# P18_USB_3_0_DRD.net
KiCad netlist of a schematic drawn in Altium Designer
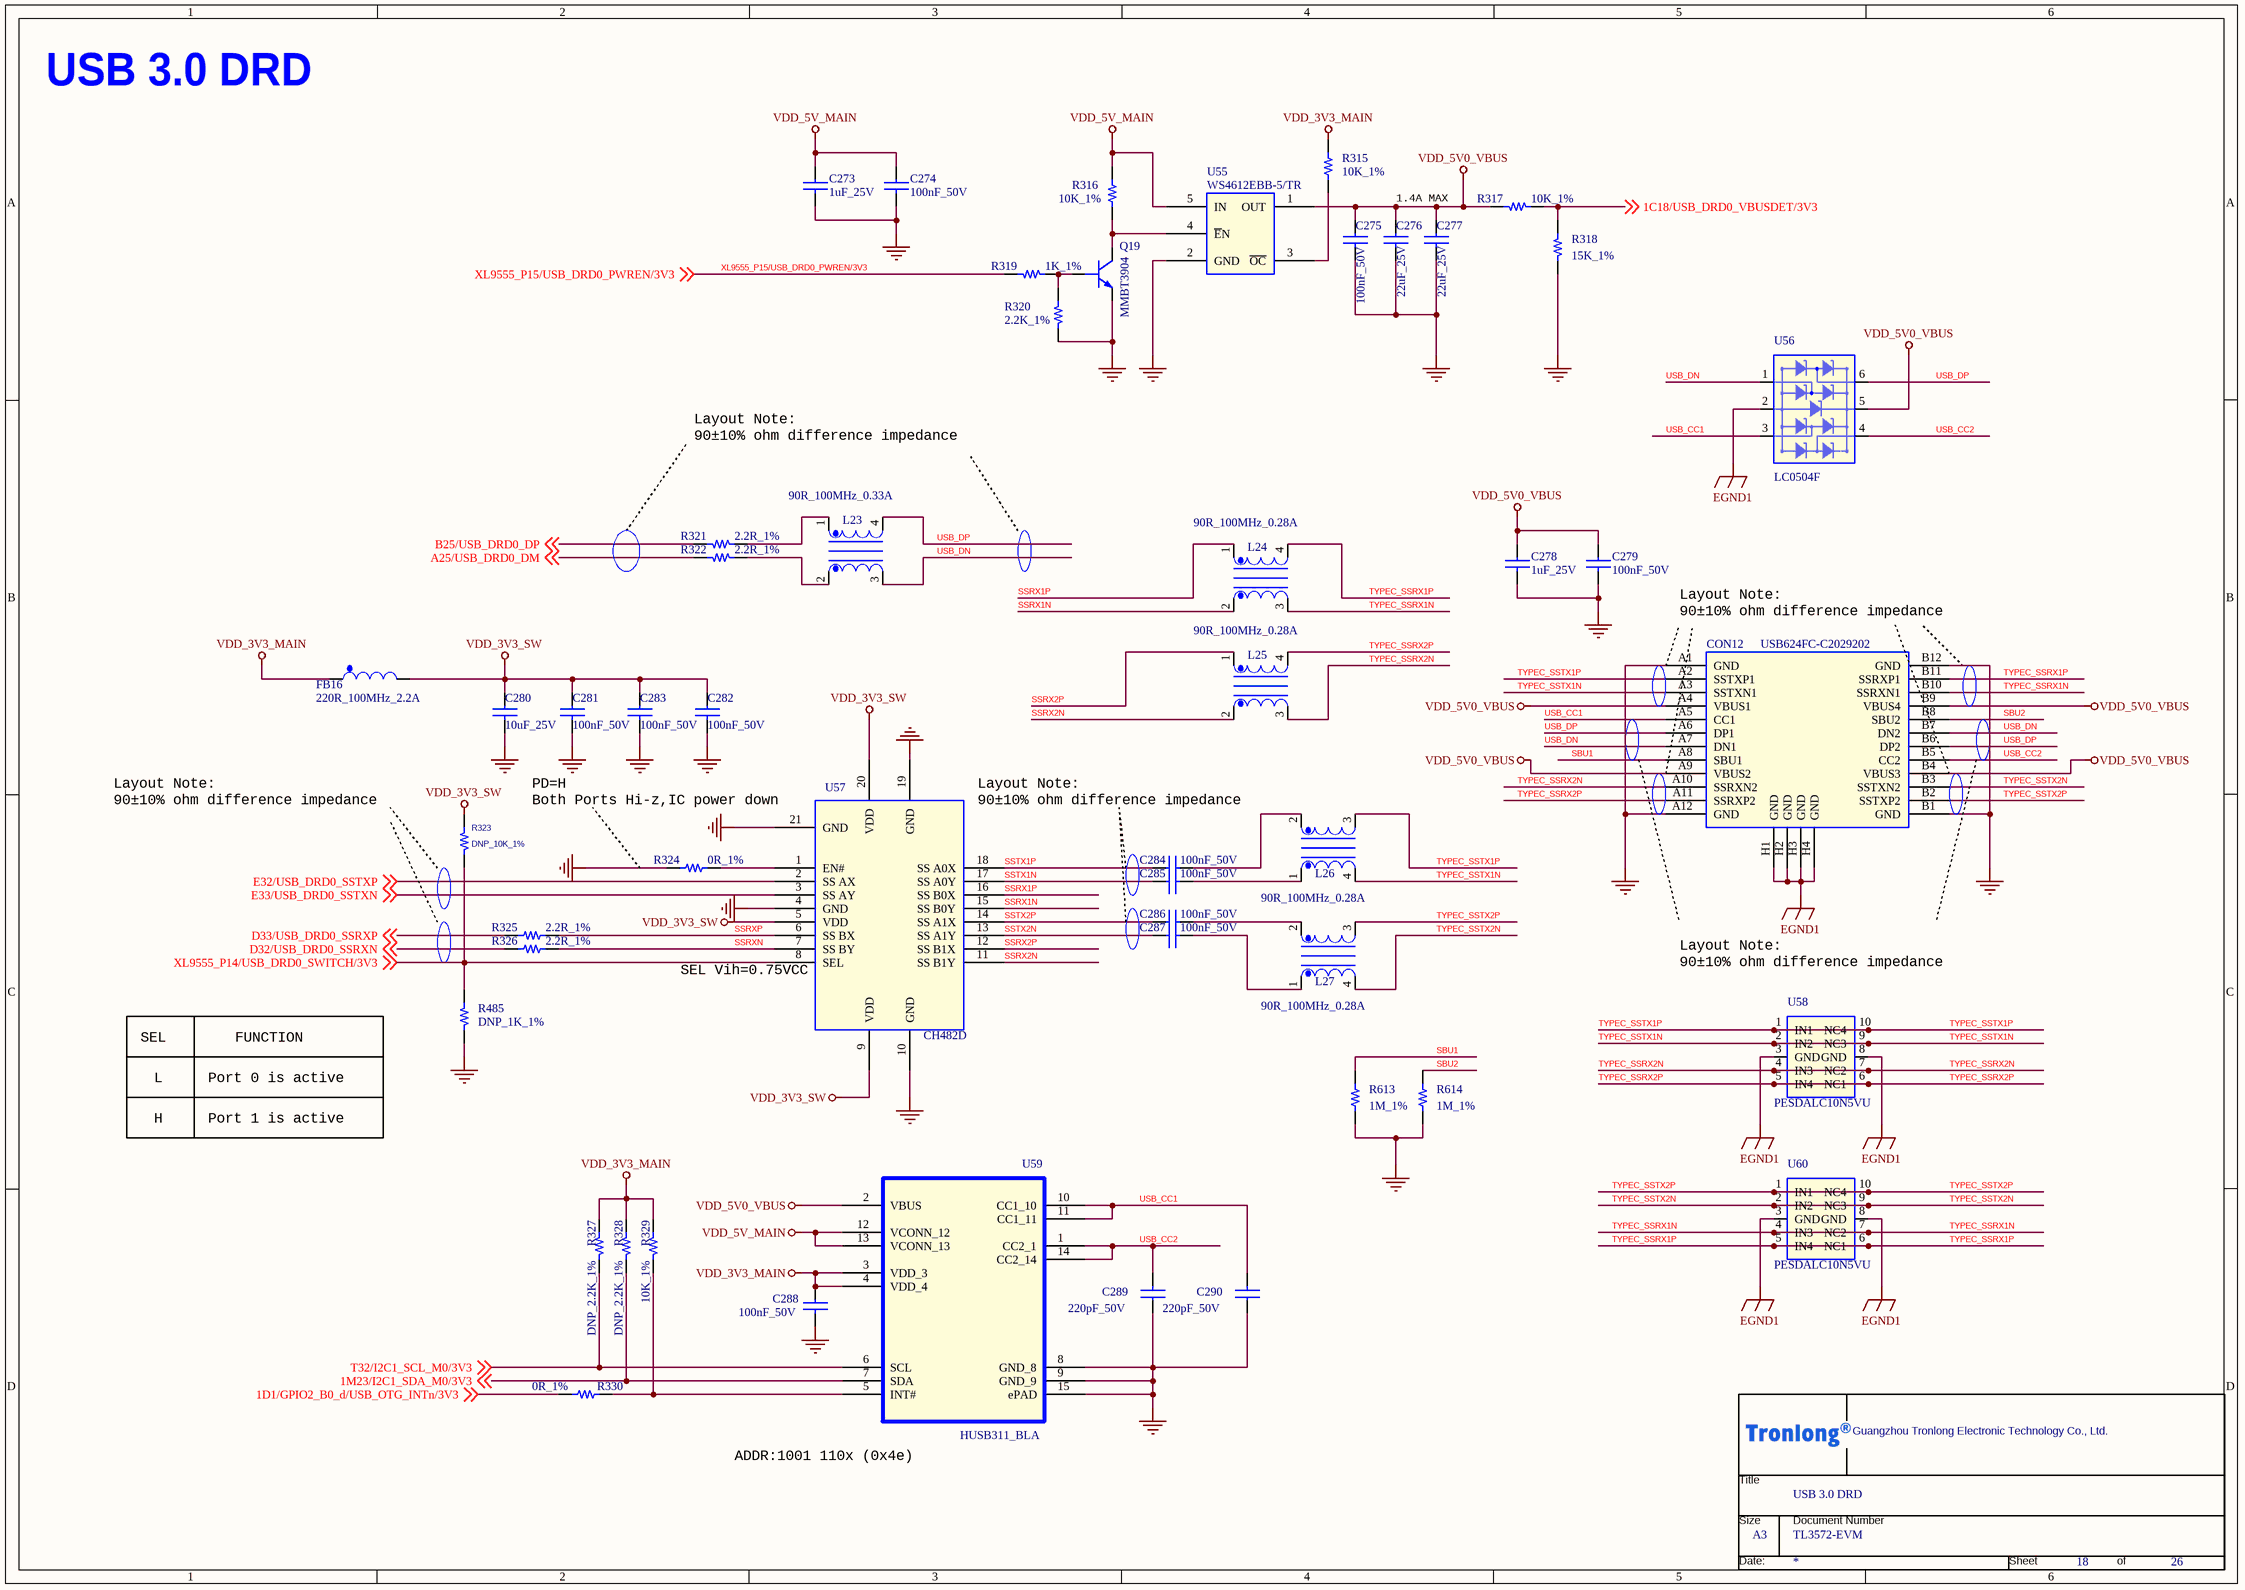
[diagram p0: P18_USB 3.0 DRD.SchDoc]

(export (version "E")
  (design (tool "Eeschema 10.0.6"))
  (components
    (comp (ref "*")
      (value "Tronlong_TITTLE_20211115")
      (fields
        (field (name "DOC") "TL3572-EVM")
        (field (name "TITLE") "USB 3.0 DRD")
        (field (name "ORGNAME") "Guangzhou Tronlong Electronic Technology Co., Ltd.")
        (field (name "PAGE SIZE") "A3")
        (field (name "PAGE NUMBER") "18")
        (field (name "PAGE COUNT") "26")
      )
      (libsource (lib "*") (part "Tronlong_TITTLE_20211115"))
    )
    (comp (ref "C273")
      (value "1uF_25V")
      (footprint "C0402")
      (description "贴片陶瓷电容,1uF,10%,25V,X5R")
      (fields
        (field (name "MANUFACTURER") "广东风华高新科技股份有限公司（FH）")
        (field (name "MANUFACTURER PARTNUMBER") "0402X105K250NT")
      )
      (libsource (lib "*") (part "CAP NP_Dup3"))
    )
    (comp (ref "C274")
      (value "100nF_50V")
      (footprint "C0402")
      (description "贴片陶瓷电容,100nF,10%,50V,X7R")
      (fields
        (field (name "MANUFACTURER") "广东风华高新科技股份有限公司（FH）")
        (field (name "MANUFACTURER PARTNUMBER") "0402B104K500NT")
      )
      (libsource (lib "*") (part "CAP NP_Dup3"))
    )
    (comp (ref "C275")
      (value "100nF_50V")
      (footprint "C0402")
      (description "贴片陶瓷电容,100nF,10%,50V,X7R")
      (fields
        (field (name "MANUFACTURER PARTNUMBER") "0402B104K500NT")
        (field (name "MANUFACTURER") "广东风华高新科技股份有限公司（FH）")
      )
      (libsource (lib "*") (part "CAP NP_Dup3"))
    )
    (comp (ref "C276")
      (value "22uF_25V")
      (footprint "C0805")
      (description "贴片陶瓷电容,22uF,20%,25V,X5R")
      (fields
        (field (name "MANUFACTURER") "广东风华高新科技股份有限公司（FH）")
        (field (name "MANUFACTURER PARTNUMBER") "0805X226M250NT")
      )
      (libsource (lib "*") (part "CAP NP_Dup3"))
    )
    (comp (ref "C277")
      (value "22uF_25V")
      (footprint "C0805")
      (description "贴片陶瓷电容,22uF,20%,25V,X5R")
      (fields
        (field (name "MANUFACTURER PARTNUMBER") "0805X226M250NT")
        (field (name "MANUFACTURER") "广东风华高新科技股份有限公司（FH）")
      )
      (libsource (lib "*") (part "CAP NP_Dup3"))
    )
    (comp (ref "C278")
      (value "1uF_25V")
      (footprint "C0402")
      (description "贴片陶瓷电容,1uF,10%,25V,X5R")
      (fields
        (field (name "MANUFACTURER PARTNUMBER") "0402X105K250NT")
        (field (name "MANUFACTURER") "广东风华高新科技股份有限公司（FH）")
      )
      (libsource (lib "*") (part "CAP NP_Dup3"))
    )
    (comp (ref "C279")
      (value "100nF_50V")
      (footprint "C0402")
      (description "贴片陶瓷电容,100nF,10%,50V,X7R")
      (fields
        (field (name "MANUFACTURER") "广东风华高新科技股份有限公司（FH）")
        (field (name "MANUFACTURER PARTNUMBER") "0402B104K500NT")
      )
      (libsource (lib "*") (part "CAP NP_Dup3"))
    )
    (comp (ref "C280")
      (value "10uF_25V")
      (footprint "C0603")
      (description "贴片陶瓷电容,10uF,20%,25V,X5R")
      (fields
        (field (name "TOLERANCE") "10%")
        (field (name "MANUFACTURER") "广东风华高新科技股份有限公司（FH）")
        (field (name "CREATED BY") "JJJ")
      )
      (libsource (lib "*") (part "CAP NP_Dup2"))
    )
    (comp (ref "C281")
      (value "100nF_50V")
      (footprint "C0402")
      (description "贴片陶瓷电容,100nF,10%,50V,X7R")
      (fields
        (field (name "MANUFACTURER") "广东风华高新科技股份有限公司（FH）")
        (field (name "MANUFACTURER PARTNUMBER") "0402B104K500NT")
      )
      (libsource (lib "*") (part "CAP NP_Dup2"))
    )
    (comp (ref "C282")
      (value "100nF_50V")
      (footprint "C0402")
      (description "贴片陶瓷电容,100nF,10%,50V,X7R")
      (fields
        (field (name "MANUFACTURER PARTNUMBER") "0402B104K500NT")
        (field (name "MANUFACTURER") "广东风华高新科技股份有限公司（FH）")
      )
      (libsource (lib "*") (part "CAP NP_Dup2"))
    )
    (comp (ref "C283")
      (value "100nF_50V")
      (footprint "C0402")
      (description "贴片陶瓷电容,100nF,10%,50V,X7R")
      (fields
        (field (name "MANUFACTURER") "广东风华高新科技股份有限公司（FH）")
        (field (name "MANUFACTURER PARTNUMBER") "0402B104K500NT")
      )
      (libsource (lib "*") (part "CAP NP_Dup2"))
    )
    (comp (ref "C284")
      (value "100nF_50V")
      (footprint "C0402")
      (description "贴片陶瓷电容,100nF,10%,50V,X7R")
      (fields
        (field (name "MANUFACTURER PARTNUMBER") "0402B104K500NT")
        (field (name "MANUFACTURER") "广东风华高新科技股份有限公司（FH）")
      )
      (libsource (lib "*") (part "CAP NP_Dup2"))
    )
    (comp (ref "C285")
      (value "100nF_50V")
      (footprint "C0402")
      (description "贴片陶瓷电容,100nF,10%,50V,X7R")
      (fields
        (field (name "MANUFACTURER") "广东风华高新科技股份有限公司（FH）")
        (field (name "MANUFACTURER PARTNUMBER") "0402B104K500NT")
      )
      (libsource (lib "*") (part "CAP NP_Dup2"))
    )
    (comp (ref "C286")
      (value "100nF_50V")
      (footprint "C0402")
      (description "贴片陶瓷电容,100nF,10%,50V,X7R")
      (fields
        (field (name "MANUFACTURER") "广东风华高新科技股份有限公司（FH）")
        (field (name "MANUFACTURER PARTNUMBER") "0402B104K500NT")
      )
      (libsource (lib "*") (part "CAP NP_Dup2"))
    )
    (comp (ref "C287")
      (value "100nF_50V")
      (footprint "C0402")
      (description "贴片陶瓷电容,100nF,10%,50V,X7R")
      (fields
        (field (name "MANUFACTURER PARTNUMBER") "0402B104K500NT")
        (field (name "MANUFACTURER") "广东风华高新科技股份有限公司（FH）")
      )
      (libsource (lib "*") (part "CAP NP_Dup2"))
    )
    (comp (ref "C288")
      (value "100nF_50V")
      (footprint "C0402")
      (description "贴片陶瓷电容,100nF,10%,50V,X7R")
      (fields
        (field (name "MANUFACTURER PARTNUMBER") "0402B104K500NT")
        (field (name "MANUFACTURER") "广东风华高新科技股份有限公司（FH）")
      )
      (libsource (lib "*") (part "CAP NP_Dup3"))
    )
    (comp (ref "C289")
      (value "220pF_50V")
      (footprint "C0402")
      (description "贴片陶瓷电容,220pF,10%,50V,X7R")
      (fields
        (field (name "MANUFACTURER") "广东风华高新科技股份有限公司（FH）")
        (field (name "MANUFACTURER PARTNUMBER") "0402B221K500NT")
      )
      (libsource (lib "*") (part "CAP NP_Dup3"))
    )
    (comp (ref "C290")
      (value "220pF_50V")
      (footprint "C0402")
      (description "贴片陶瓷电容,220pF,10%,50V,X7R")
      (fields
        (field (name "MANUFACTURER PARTNUMBER") "0402B221K500NT")
        (field (name "MANUFACTURER") "广东风华高新科技股份有限公司（FH）")
      )
      (libsource (lib "*") (part "CAP NP_Dup3"))
    )
    (comp (ref "CON12")
      (value "USB624FC-C2029202")
      (footprint "TYPE-C_24P_180_SMD")
      (description "USB TYPE C 24P FEMALE SMT 侧贴 带定位柱 双壳点焊带弹弯脚 L=14.30 CH=5.06")
      (fields (field (name "MANUFACTURER") "深圳市爱特姆科技有限公司（ATOM）"))
      (libsource (lib "*") (part "usb 3_1.0 type-c female"))
    )
    (comp (ref "FB16")
      (value "220R_100MHz_2.2A")
      (footprint "L0603")
      (description "磁珠,50mΩ,2.2A,220R@100MHz")
      (fields
        (field (name "MANUFACTURER PARTNUMBER") "UPZ1608U221-2R2TF")
        (field (name "MANUFACTURER") "深圳顺络电子股份有限公司（Sunlord）")
      )
      (libsource (lib "*") (part "FERRITE BEAD"))
    )
    (comp (ref "L23")
      (value "90R_100MHz_0.33A")
      (footprint "SMD-L2012M-4P")
      (description "贴片共模电感,350mΩ,0.33A,50V,90Ω@100MHz")
      (fields
        (field (name "MANUFACTURER") "深圳顺络电子股份有限公司（Sunlord）")
        (field (name "MANUFACTURER PARTNUMBER") "SDCW2012-2-900TF")
      )
      (libsource (lib "") (part "TFR_AXA_A_1_1"))
    )
    (comp (ref "L24")
      (value "90R_100MHz_0.28A")
      (footprint "SMD-L2012M-4P")
      (description "贴片共模电感,400mΩ,0.28A,20V,90Ω@100MHz")
      (fields
        (field (name "MANUFACTURER PARTNUMBER") "SDCW2012U-2-900TF")
        (field (name "MANUFACTURER") "深圳顺络电子股份有限公司（Sunlord）")
      )
      (libsource (lib "") (part "TFR_AXA_A_1_1"))
    )
    (comp (ref "L25")
      (value "90R_100MHz_0.28A")
      (footprint "SMD-L2012M-4P")
      (description "贴片共模电感,400mΩ,0.28A,20V,90Ω@100MHz")
      (fields
        (field (name "MANUFACTURER PARTNUMBER") "SDCW2012U-2-900TF")
        (field (name "MANUFACTURER") "深圳顺络电子股份有限公司（Sunlord）")
      )
      (libsource (lib "") (part "TFR_AXA_A_1_1"))
    )
    (comp (ref "L26")
      (value "90R_100MHz_0.28A")
      (footprint "SMD-L2012M-4P")
      (description "贴片共模电感,400mΩ,0.28A,20V,90Ω@100MHz")
      (fields
        (field (name "MANUFACTURER") "深圳顺络电子股份有限公司（Sunlord）")
        (field (name "MANUFACTURER PARTNUMBER") "SDCW2012U-2-900TF")
      )
      (libsource (lib "*") (part "TFR_AXA_A_1"))
    )
    (comp (ref "L27")
      (value "90R_100MHz_0.28A")
      (footprint "SMD-L2012M-4P")
      (description "贴片共模电感,400mΩ,0.28A,20V,90Ω@100MHz")
      (fields
        (field (name "MANUFACTURER") "深圳顺络电子股份有限公司（Sunlord）")
        (field (name "MANUFACTURER PARTNUMBER") "SDCW2012U-2-900TF")
      )
      (libsource (lib "*") (part "TFR_AXA_A_1"))
    )
    (comp (ref "Q19")
      (value "MMBT3904")
      (footprint "SOT23-3_DBZ3")
      (description "BJT,NPN,Vceo=40V,Ic=200mA,fT=300MHz,PD=200mW")
      (fields (field (name "MANUFACTURER") "江苏长晶科技股份有限公司（JSCJ）"))
      (libsource (lib "*") (part "MMBT3904/SOT"))
    )
    (comp (ref "R315")
      (value "10K_1%")
      (footprint "R0402")
      (description "贴片电阻,10K,±1%,1/16W")
      (fields
        (field (name "MANUFACTURER") "广东风华高新科技股份有限公司（FH）")
        (field (name "MANUFACTURER PARTNUMBER") "RC-02K1002FT")
      )
      (libsource (lib "*") (part "Resistor_Dup4"))
    )
    (comp (ref "R316")
      (value "10K_1%")
      (footprint "R0402")
      (description "贴片电阻,10K,±1%,1/16W")
      (fields
        (field (name "MANUFACTURER PARTNUMBER") "RC-02K1002FT")
        (field (name "MANUFACTURER") "广东风华高新科技股份有限公司（FH）")
      )
      (libsource (lib "*") (part "Resistor_Dup4"))
    )
    (comp (ref "R317")
      (value "10K_1%")
      (footprint "R0402")
      (description "贴片电阻,10K,±1%,1/16W")
      (fields
        (field (name "MANUFACTURER") "广东风华高新科技股份有限公司（FH）")
        (field (name "MANUFACTURER PARTNUMBER") "RC-02K1002FT")
      )
      (libsource (lib "*") (part "Resistor_Dup3"))
    )
    (comp (ref "R318")
      (value "15K_1%")
      (footprint "R0402")
      (description "贴片电阻,15K,±1%,1/16W")
      (fields
        (field (name "MANUFACTURER PARTNUMBER") "RC-02K1502FT")
        (field (name "MANUFACTURER") "广东风华高新科技股份有限公司（FH）")
      )
      (libsource (lib "*") (part "Resistor_Dup3"))
    )
    (comp (ref "R319")
      (value "1K_1%")
      (footprint "R0603")
      (description "贴片电阻,1K,±1%,1/10W")
      (fields
        (field (name "MANUFACTURER PARTNUMBER") "RS-03K1001FT")
        (field (name "MANUFACTURER") "广东风华高新科技股份有限公司（FH）")
      )
      (libsource (lib "*") (part "Resistor_Dup4"))
    )
    (comp (ref "R320")
      (value "2.2K_1%")
      (footprint "R0603")
      (description "贴片电阻,2.2K,±1%,1/10W")
      (fields
        (field (name "MANUFACTURER PARTNUMBER") "RS-03K2201FT")
        (field (name "MANUFACTURER") "广东风华高新科技股份有限公司（FH）")
      )
      (libsource (lib "*") (part "Resistor_Dup4"))
    )
    (comp (ref "R321")
      (value "2.2R_1%")
      (footprint "R0402")
      (description "贴片电阻,2.2R,±1%,1/16W")
      (fields
        (field (name "MANUFACTURER") "广东风华高新科技股份有限公司（FH）")
        (field (name "MANUFACTURER PARTNUMBER") "RC-02U2R20FT")
      )
      (libsource (lib "*") (part "Resistor_Dup4"))
    )
    (comp (ref "R322")
      (value "2.2R_1%")
      (footprint "R0402")
      (description "贴片电阻,2.2R,±1%,1/16W")
      (fields
        (field (name "MANUFACTURER") "广东风华高新科技股份有限公司（FH）")
        (field (name "MANUFACTURER PARTNUMBER") "RC-02U2R20FT")
      )
      (libsource (lib "*") (part "Resistor_Dup4"))
    )
    (comp (ref "R323")
      (value "DNP_10K_1%")
      (footprint "R0402")
      (description "贴片电阻,10K,±1%,1/16W")
      (fields
        (field (name "MANUFACTURER") "广东风华高新科技股份有限公司（FH）")
        (field (name "MANUFACTURER PARTNUMBER") "RC-02K1002FT")
      )
      (libsource (lib "*") (part "Resistor_Dup3"))
    )
    (comp (ref "R324")
      (value "0R_1%")
      (footprint "R0402")
      (description "贴片电阻,0R,±1%,1/16W")
      (fields
        (field (name "MANUFACTURER PARTNUMBER") "RC-02000FT")
        (field (name "MANUFACTURER") "广东风华高新科技股份有限公司（FH）")
      )
      (libsource (lib "*") (part "Resistor_Dup3"))
    )
    (comp (ref "R325")
      (value "2.2R_1%")
      (footprint "R0402")
      (description "贴片电阻,2.2R,±1%,1/16W")
      (fields
        (field (name "MANUFACTURER") "广东风华高新科技股份有限公司（FH）")
        (field (name "MANUFACTURER PARTNUMBER") "RC-02U2R20FT")
      )
      (libsource (lib "*") (part "Resistor_Dup3"))
    )
    (comp (ref "R326")
      (value "2.2R_1%")
      (footprint "R0402")
      (description "贴片电阻,2.2R,±1%,1/16W")
      (fields
        (field (name "MANUFACTURER") "广东风华高新科技股份有限公司（FH）")
        (field (name "MANUFACTURER PARTNUMBER") "RC-02U2R20FT")
      )
      (libsource (lib "*") (part "Resistor_Dup3"))
    )
    (comp (ref "R327")
      (value "DNP_2.2K_1%")
      (footprint "R0402")
      (description "贴片电阻,2.2K,±1%,1/16W")
      (fields
        (field (name "MANUFACTURER") "广东风华高新科技股份有限公司（FH）")
        (field (name "MANUFACTURER PARTNUMBER") "RC-02K2201FT")
      )
      (libsource (lib "*") (part "Resistor_Dup4"))
    )
    (comp (ref "R328")
      (value "DNP_2.2K_1%")
      (footprint "R0402")
      (description "贴片电阻,2.2K,±1%,1/16W")
      (fields
        (field (name "MANUFACTURER PARTNUMBER") "RC-02K2201FT")
        (field (name "MANUFACTURER") "广东风华高新科技股份有限公司（FH）")
      )
      (libsource (lib "*") (part "Resistor_Dup4"))
    )
    (comp (ref "R329")
      (value "10K_1%")
      (footprint "R0402")
      (description "贴片电阻,10K,±1%,1/16W")
      (fields
        (field (name "MANUFACTURER PARTNUMBER") "RC-02K1002FT")
        (field (name "MANUFACTURER") "广东风华高新科技股份有限公司（FH）")
      )
      (libsource (lib "*") (part "Resistor_Dup4"))
    )
    (comp (ref "R330")
      (value "0R_1%")
      (footprint "R0402")
      (description "贴片电阻,0R,±1%,1/16W")
      (fields
        (field (name "MANUFACTURER PARTNUMBER") "RC-02000FT")
        (field (name "MANUFACTURER") "广东风华高新科技股份有限公司（FH）")
      )
      (libsource (lib "*") (part "Resistor_Dup3"))
    )
    (comp (ref "R485")
      (value "DNP_1K_1%")
      (footprint "R0603")
      (description "贴片电阻,2.2K,±1%,1/10W")
      (fields
        (field (name "MANUFACTURER PARTNUMBER") "RS-03K2201FT")
        (field (name "MANUFACTURER") "广东风华高新科技股份有限公司（FH）")
      )
      (libsource (lib "*") (part "Resistor_Dup4"))
    )
    (comp (ref "R613")
      (value "1M_1%")
      (footprint "R0402")
      (description "RC0402FR-071ML,0402WGF1004TCE")
      (fields
        (field (name "MANUFACTURER") "广州创龙")
        (field (name "MANUFACTURER PARTNUMBER") "1M,±1%,R0402,≥1/16W")
      )
      (libsource (lib "*") (part "Resistor_Dup3"))
    )
    (comp (ref "R614")
      (value "1M_1%")
      (footprint "R0402")
      (description "RC0402FR-071ML,0402WGF1004TCE")
      (fields
        (field (name "MANUFACTURER") "广州创龙")
        (field (name "MANUFACTURER PARTNUMBER") "1M,±1%,R0402,≥1/16W")
      )
      (libsource (lib "*") (part "Resistor_Dup3"))
    )
    (comp (ref "U55")
      (value "WS4612EBB-5/TR")
      (footprint "SOT23-5")
      (description "限流配电开关,2.5V~5.5V,1.4A")
      (fields (field (name "MANUFACTURER") "上海韦尔半导体股份有限公司（WILLSEMI）"))
      (libsource (lib "*") (part "TPS2041BDGN_0"))
    )
    (comp (ref "U56")
      (value "LC0504F")
      (footprint "SOT363")
      (description "ESD二极管,VRWM=5V,VBR=6V,四组,单向,8KV,15KV")
      (fields (field (name "MANUFACTURER") "上海雷卯电子科技有限公司（Leiditech）"))
      (libsource (lib "*") (part "PRTR5V0U4Y"))
    )
    (comp (ref "U57")
      (value "CH482D")
      (footprint "qfn2545-20-ch482d")
      (description "两路2选1模拟开关复用器")
      (fields (field (name "MANUFACTURER") "南京沁恒微电子股份有限公司（WCH）"))
      (libsource (lib "*") (part "CH482D"))
    )
    (comp (ref "U58")
      (value "PESDALC10N5VU")
      (footprint "DFN-10-2510")
      (description "ESD二极管,VRWM=5V,VBR=6V,四组,单向,15KV,30KV")
      (fields (field (name "MANUFACTURER") "上海芯导电子科技股份有限公司（Prisemi）"))
      (libsource (lib "*") (part "SU099PGTR"))
    )
    (comp (ref "U59")
      (value "HUSB311_BLA")
      (footprint "MLP14_2R50X2R50X0R80")
      (description "USB Type-C PD 控制器")
      (fields (field (name "MANUFACTURER") "深圳慧能泰半导体科技有限公司（Hynetek）") (field (name "CREATED BY") "JJJ"))
      (libsource (lib "*") (part "USB_FUSB302B"))
    )
    (comp (ref "U60")
      (value "PESDALC10N5VU")
      (footprint "DFN-10-2510")
      (description "ESD二极管,VRWM=5V,VBR=6V,四组,单向,15KV,30KV")
      (fields (field (name "MANUFACTURER") "上海芯导电子科技股份有限公司（Prisemi）"))
      (libsource (lib "*") (part "SU099PGTR"))
    )
  )
  (nets
    (net (code "1") (name "/SBU1") (class "Default")
      (node (ref "CON12") (pin "A8") (pinfunction "SBU1_A8") (pintype "passive"))
      (node (ref "R613") (pin "1") (pinfunction "1_1") (pintype "passive"))
    )
    (net (code "2") (name "/SBU2") (class "Default")
      (node (ref "CON12") (pin "B8") (pinfunction "SBU2_B8") (pintype "passive"))
      (node (ref "R614") (pin "1") (pinfunction "1_1") (pintype "passive"))
    )
    (net (code "3") (name "/SSRX1N") (class "Default")
      (node (ref "L24") (pin "2") (pinfunction "2_2") (pintype "passive"))
      (node (ref "U57") (pin "15") (pinfunction "SS_B0Y_15") (pintype "passive"))
    )
    (net (code "4") (name "/SSRX1P") (class "Default")
      (node (ref "L24") (pin "1") (pinfunction "1_1") (pintype "passive"))
      (node (ref "U57") (pin "16") (pinfunction "SS_B0X_16") (pintype "passive"))
    )
    (net (code "5") (name "/SSRX2N") (class "Default")
      (node (ref "L25") (pin "2") (pinfunction "2_2") (pintype "passive"))
      (node (ref "U57") (pin "11") (pinfunction "SS_B1Y_11") (pintype "passive"))
    )
    (net (code "6") (name "/SSRX2P") (class "Default")
      (node (ref "L25") (pin "1") (pinfunction "1_1") (pintype "passive"))
      (node (ref "U57") (pin "12") (pinfunction "SS_B1X_12") (pintype "passive"))
    )
    (net (code "7") (name "/SSRXN") (class "Default")
      (node (ref "R326") (pin "2") (pinfunction "2_2") (pintype "passive"))
      (node (ref "U57") (pin "7") (pinfunction "SS_BY_7") (pintype "passive"))
    )
    (net (code "8") (name "/SSRXP") (class "Default")
      (node (ref "R325") (pin "2") (pinfunction "2_2") (pintype "passive"))
      (node (ref "U57") (pin "6") (pinfunction "SS_BX_6") (pintype "passive"))
    )
    (net (code "9") (name "/SSTX1N") (class "Default")
      (node (ref "C285") (pin "1") (pinfunction "1_1") (pintype "passive"))
      (node (ref "U57") (pin "17") (pinfunction "SS_A0Y_17") (pintype "passive"))
    )
    (net (code "10") (name "/SSTX1P") (class "Default")
      (node (ref "C284") (pin "1") (pinfunction "1_1") (pintype "passive"))
      (node (ref "U57") (pin "18") (pinfunction "SS_A0X_18") (pintype "passive"))
    )
    (net (code "11") (name "/SSTX2N") (class "Default")
      (node (ref "C287") (pin "1") (pinfunction "1_1") (pintype "passive"))
      (node (ref "U57") (pin "13") (pinfunction "SS_A1Y_13") (pintype "passive"))
    )
    (net (code "12") (name "/SSTX2P") (class "Default")
      (node (ref "C286") (pin "1") (pinfunction "1_1") (pintype "passive"))
      (node (ref "U57") (pin "14") (pinfunction "SS_A1X_14") (pintype "passive"))
    )
    (net (code "13") (name "/TYPEC_SSRX1N") (class "Default")
      (node (ref "CON12") (pin "B10") (pinfunction "SSRXN1_B10") (pintype "passive"))
      (node (ref "L24") (pin "3") (pinfunction "3_3") (pintype "passive"))
      (node (ref "U60") (pin "4") (pinfunction "IN3_4") (pintype "passive"))
      (node (ref "U60") (pin "7") (pinfunction "NC2_7") (pintype "passive"))
    )
    (net (code "14") (name "/TYPEC_SSRX1P") (class "Default")
      (node (ref "CON12") (pin "B11") (pinfunction "SSRXP1_B11") (pintype "passive"))
      (node (ref "L24") (pin "4") (pinfunction "4_4") (pintype "passive"))
      (node (ref "U60") (pin "5") (pinfunction "IN4_5") (pintype "passive"))
      (node (ref "U60") (pin "6") (pinfunction "NC1_6") (pintype "passive"))
    )
    (net (code "15") (name "/TYPEC_SSRX2N") (class "Default")
      (node (ref "CON12") (pin "A10") (pinfunction "SSRXN2_A10") (pintype "passive"))
      (node (ref "L25") (pin "3") (pinfunction "3_3") (pintype "passive"))
      (node (ref "U58") (pin "4") (pinfunction "IN3_4") (pintype "passive"))
      (node (ref "U58") (pin "7") (pinfunction "NC2_7") (pintype "passive"))
    )
    (net (code "16") (name "/TYPEC_SSRX2P") (class "Default")
      (node (ref "CON12") (pin "A11") (pinfunction "SSRXP2_A11") (pintype "passive"))
      (node (ref "L25") (pin "4") (pinfunction "4_4") (pintype "passive"))
      (node (ref "U58") (pin "5") (pinfunction "IN4_5") (pintype "passive"))
      (node (ref "U58") (pin "6") (pinfunction "NC1_6") (pintype "passive"))
    )
    (net (code "17") (name "/TYPEC_SSTX1N") (class "Default")
      (node (ref "CON12") (pin "A3") (pinfunction "SSTXN1_A3") (pintype "passive"))
      (node (ref "L26") (pin "4") (pinfunction "4_4") (pintype "passive"))
      (node (ref "U58") (pin "2") (pinfunction "IN2_2") (pintype "passive"))
      (node (ref "U58") (pin "9") (pinfunction "NC3_9") (pintype "passive"))
    )
    (net (code "18") (name "/TYPEC_SSTX1P") (class "Default")
      (node (ref "CON12") (pin "A2") (pinfunction "SSTXP1_A2") (pintype "passive"))
      (node (ref "L26") (pin "3") (pinfunction "3_3") (pintype "passive"))
      (node (ref "U58") (pin "1") (pinfunction "IN1_1") (pintype "passive"))
      (node (ref "U58") (pin "10") (pinfunction "NC4_10") (pintype "passive"))
    )
    (net (code "19") (name "/TYPEC_SSTX2N") (class "Default")
      (node (ref "CON12") (pin "B3") (pinfunction "SSTXN2_B3") (pintype "passive"))
      (node (ref "L27") (pin "4") (pinfunction "4_4") (pintype "passive"))
      (node (ref "U60") (pin "2") (pinfunction "IN2_2") (pintype "passive"))
      (node (ref "U60") (pin "9") (pinfunction "NC3_9") (pintype "passive"))
    )
    (net (code "20") (name "/TYPEC_SSTX2P") (class "Default")
      (node (ref "CON12") (pin "B2") (pinfunction "SSTXP2_B2") (pintype "passive"))
      (node (ref "L27") (pin "3") (pinfunction "3_3") (pintype "passive"))
      (node (ref "U60") (pin "1") (pinfunction "IN1_1") (pintype "passive"))
      (node (ref "U60") (pin "10") (pinfunction "NC4_10") (pintype "passive"))
    )
    (net (code "21") (name "/USB_CC1") (class "Default")
      (node (ref "C290") (pin "2") (pinfunction "2_2") (pintype "passive"))
      (node (ref "CON12") (pin "A5") (pinfunction "CC1_A5") (pintype "passive"))
      (node (ref "U56") (pin "3") (pinfunction "3_3") (pintype "passive"))
      (node (ref "U59") (pin "10") (pinfunction "CC1_10_10") (pintype "passive"))
      (node (ref "U59") (pin "11") (pinfunction "CC1_11_11") (pintype "passive"))
    )
    (net (code "22") (name "/USB_CC2") (class "Default")
      (node (ref "C289") (pin "2") (pinfunction "2_2") (pintype "passive"))
      (node (ref "CON12") (pin "B5") (pinfunction "CC2_B5") (pintype "passive"))
      (node (ref "U56") (pin "4") (pinfunction "4_4") (pintype "passive"))
      (node (ref "U59") (pin "1") (pinfunction "CC2_1_1") (pintype "passive"))
      (node (ref "U59") (pin "14") (pinfunction "CC2_14_14") (pintype "passive"))
    )
    (net (code "23") (name "/USB_DN") (class "Default")
      (node (ref "CON12") (pin "A7") (pinfunction "DN1_A7") (pintype "passive"))
      (node (ref "CON12") (pin "B7") (pinfunction "DN2_B7") (pintype "passive"))
      (node (ref "L23") (pin "3") (pinfunction "3_3") (pintype "passive"))
      (node (ref "U56") (pin "1") (pinfunction "1_1") (pintype "passive"))
    )
    (net (code "24") (name "/USB_DP") (class "Default")
      (node (ref "CON12") (pin "A6") (pinfunction "DP1_A6") (pintype "passive"))
      (node (ref "CON12") (pin "B6") (pinfunction "DP2_B6") (pintype "passive"))
      (node (ref "L23") (pin "4") (pinfunction "4_4") (pintype "passive"))
      (node (ref "U56") (pin "6") (pinfunction "6_6") (pintype "passive"))
    )
    (net (code "25") (name "1C18{slash}USB_DRD0_VBUSDET{slash}3V3") (class "Default")
      (node (ref "R317") (pin "1") (pinfunction "1_1") (pintype "passive"))
      (node (ref "R318") (pin "1") (pinfunction "1_1") (pintype "passive"))
    )
    (net (code "26") (name "1D1{slash}GPIO2_B0_d{slash}USB_OTG_INTn{slash}3V3") (class "Default")
      (node (ref "R330") (pin "1") (pinfunction "1_1") (pintype "passive"))
    )
    (net (code "27") (name "1M23{slash}I2C1_SDA_M0{slash}3V3") (class "Default")
      (node (ref "R328") (pin "2") (pinfunction "2_2") (pintype "passive"))
      (node (ref "U59") (pin "7") (pinfunction "SDA_7") (pintype "passive"))
    )
    (net (code "28") (name "A25{slash}USB_DRD0_DM") (class "Default")
      (node (ref "R322") (pin "1") (pinfunction "1_1") (pintype "passive"))
    )
    (net (code "29") (name "B25{slash}USB_DRD0_DP") (class "Default")
      (node (ref "R321") (pin "1") (pinfunction "1_1") (pintype "passive"))
    )
    (net (code "30") (name "D32{slash}USB_DRD0_SSRXN") (class "Default")
      (node (ref "R326") (pin "1") (pinfunction "1_1") (pintype "passive"))
    )
    (net (code "31") (name "D33{slash}USB_DRD0_SSRXP") (class "Default")
      (node (ref "R325") (pin "1") (pinfunction "1_1") (pintype "passive"))
    )
    (net (code "32") (name "E32{slash}USB_DRD0_SSTXP") (class "Default")
      (node (ref "U57") (pin "2") (pinfunction "SS_AX_2") (pintype "passive"))
    )
    (net (code "33") (name "E33{slash}USB_DRD0_SSTXN") (class "Default")
      (node (ref "U57") (pin "3") (pinfunction "SS_AY_3") (pintype "passive"))
    )
    (net (code "34") (name "EGND1") (class "Default")
      (node (ref "CON12") (pin "H1") (pinfunction "GND_H1") (pintype "power_in"))
      (node (ref "CON12") (pin "H2") (pinfunction "GND_H2") (pintype "power_in"))
      (node (ref "CON12") (pin "H3") (pinfunction "GND_H3") (pintype "power_in"))
      (node (ref "CON12") (pin "H4") (pinfunction "GND_H4") (pintype "power_in"))
      (node (ref "U56") (pin "2") (pinfunction "2_2") (pintype "passive"))
      (node (ref "U58") (pin "3") (pinfunction "GND_3") (pintype "power_in"))
      (node (ref "U58") (pin "8") (pinfunction "GND_8") (pintype "power_in"))
      (node (ref "U60") (pin "3") (pinfunction "GND_3") (pintype "power_in"))
      (node (ref "U60") (pin "8") (pinfunction "GND_8") (pintype "power_in"))
    )
    (net (code "35") (name "GND") (class "Default")
      (node (ref "C273") (pin "2") (pinfunction "2_2") (pintype "passive"))
      (node (ref "C274") (pin "2") (pinfunction "2_2") (pintype "passive"))
      (node (ref "C275") (pin "2") (pinfunction "2_2") (pintype "passive"))
      (node (ref "C276") (pin "2") (pinfunction "2_2") (pintype "passive"))
      (node (ref "C277") (pin "2") (pinfunction "2_2") (pintype "passive"))
      (node (ref "C278") (pin "2") (pinfunction "2_2") (pintype "passive"))
      (node (ref "C279") (pin "2") (pinfunction "2_2") (pintype "passive"))
      (node (ref "C280") (pin "2") (pinfunction "2_2") (pintype "passive"))
      (node (ref "C281") (pin "2") (pinfunction "2_2") (pintype "passive"))
      (node (ref "C282") (pin "2") (pinfunction "2_2") (pintype "passive"))
      (node (ref "C283") (pin "2") (pinfunction "2_2") (pintype "passive"))
      (node (ref "C288") (pin "2") (pinfunction "2_2") (pintype "passive"))
      (node (ref "C289") (pin "1") (pinfunction "1_1") (pintype "passive"))
      (node (ref "C290") (pin "1") (pinfunction "1_1") (pintype "passive"))
      (node (ref "CON12") (pin "A1") (pinfunction "GND_A1") (pintype "power_in"))
      (node (ref "CON12") (pin "A12") (pinfunction "GND_A12") (pintype "power_in"))
      (node (ref "CON12") (pin "B1") (pinfunction "GND_B1") (pintype "power_in"))
      (node (ref "CON12") (pin "B12") (pinfunction "GND_B12") (pintype "power_in"))
      (node (ref "Q19") (pin "2") (pinfunction "E_2") (pintype "passive"))
      (node (ref "R318") (pin "2") (pinfunction "2_2") (pintype "passive"))
      (node (ref "R320") (pin "2") (pinfunction "2_2") (pintype "passive"))
      (node (ref "R324") (pin "1") (pinfunction "1_1") (pintype "passive"))
      (node (ref "R485") (pin "2") (pinfunction "2_2") (pintype "passive"))
      (node (ref "R613") (pin "2") (pinfunction "2_2") (pintype "passive"))
      (node (ref "R614") (pin "2") (pinfunction "2_2") (pintype "passive"))
      (node (ref "U55") (pin "2") (pinfunction "GND_2") (pintype "passive"))
      (node (ref "U57") (pin "10") (pinfunction "GND_10") (pintype "power_in"))
      (node (ref "U57") (pin "19") (pinfunction "GND_19") (pintype "power_in"))
      (node (ref "U57") (pin "21") (pinfunction "GND_21") (pintype "power_in"))
      (node (ref "U57") (pin "4") (pinfunction "GND_4") (pintype "power_in"))
      (node (ref "U59") (pin "15") (pinfunction "ePAD_15") (pintype "power_in"))
      (node (ref "U59") (pin "8") (pinfunction "GND_8_8") (pintype "power_in"))
      (node (ref "U59") (pin "9") (pinfunction "GND_9_9") (pintype "power_in"))
    )
    (net (code "36") (name "Net-(C284-Pad2)") (class "Default")
      (node (ref "C284") (pin "2") (pinfunction "2_2") (pintype "passive"))
      (node (ref "L26") (pin "2") (pinfunction "2_2") (pintype "passive"))
    )
    (net (code "37") (name "Net-(C285-Pad2)") (class "Default")
      (node (ref "C285") (pin "2") (pinfunction "2_2") (pintype "passive"))
      (node (ref "L26") (pin "1") (pinfunction "1_1") (pintype "passive"))
    )
    (net (code "38") (name "Net-(C286-Pad2)") (class "Default")
      (node (ref "C286") (pin "2") (pinfunction "2_2") (pintype "passive"))
      (node (ref "L27") (pin "2") (pinfunction "2_2") (pintype "passive"))
    )
    (net (code "39") (name "Net-(C287-Pad2)") (class "Default")
      (node (ref "C287") (pin "2") (pinfunction "2_2") (pintype "passive"))
      (node (ref "L27") (pin "1") (pinfunction "1_1") (pintype "passive"))
    )
    (net (code "40") (name "Net-(L23-Pad1)") (class "Default")
      (node (ref "L23") (pin "1") (pinfunction "1_1") (pintype "passive"))
      (node (ref "R321") (pin "2") (pinfunction "2_2") (pintype "passive"))
    )
    (net (code "41") (name "Net-(L23-Pad2)") (class "Default")
      (node (ref "L23") (pin "2") (pinfunction "2_2") (pintype "passive"))
      (node (ref "R322") (pin "2") (pinfunction "2_2") (pintype "passive"))
    )
    (net (code "42") (name "Net-(Q19-B)") (class "Default")
      (node (ref "Q19") (pin "1") (pinfunction "B_1") (pintype "passive"))
      (node (ref "R319") (pin "2") (pinfunction "2_2") (pintype "passive"))
      (node (ref "R320") (pin "1") (pinfunction "1_1") (pintype "passive"))
    )
    (net (code "43") (name "Net-(Q19-C)") (class "Default")
      (node (ref "Q19") (pin "3") (pinfunction "C_3") (pintype "passive"))
      (node (ref "R316") (pin "2") (pinfunction "2_2") (pintype "passive"))
      (node (ref "U55") (pin "4") (pinfunction "~{E}N_4") (pintype "passive"))
    )
    (net (code "44") (name "Net-(U55-~{OC})") (class "Default")
      (node (ref "R315") (pin "1") (pinfunction "1_1") (pintype "passive"))
      (node (ref "U55") (pin "3") (pinfunction "~{OC}_3") (pintype "passive"))
    )
    (net (code "45") (name "Net-(U57-EN#)") (class "Default")
      (node (ref "R324") (pin "2") (pinfunction "2_2") (pintype "passive"))
      (node (ref "U57") (pin "1") (pinfunction "EN#_1") (pintype "passive"))
    )
    (net (code "46") (name "Net-(U59-INT#)") (class "Default")
      (node (ref "R329") (pin "2") (pinfunction "2_2") (pintype "passive"))
      (node (ref "R330") (pin "2") (pinfunction "2_2") (pintype "passive"))
      (node (ref "U59") (pin "5") (pinfunction "INT#_5") (pintype "passive"))
    )
    (net (code "47") (name "T32{slash}I2C1_SCL_M0{slash}3V3") (class "Default")
      (node (ref "R327") (pin "2") (pinfunction "2_2") (pintype "passive"))
      (node (ref "U59") (pin "6") (pinfunction "SCL_6") (pintype "passive"))
    )
    (net (code "48") (name "VDD_3V3_MAIN") (class "Default")
      (node (ref "C288") (pin "1") (pinfunction "1_1") (pintype "passive"))
      (node (ref "FB16") (pin "1") (pinfunction "1_1") (pintype "passive"))
      (node (ref "R315") (pin "2") (pinfunction "2_2") (pintype "passive"))
      (node (ref "R327") (pin "1") (pinfunction "1_1") (pintype "passive"))
      (node (ref "R328") (pin "1") (pinfunction "1_1") (pintype "passive"))
      (node (ref "R329") (pin "1") (pinfunction "1_1") (pintype "passive"))
      (node (ref "U59") (pin "3") (pinfunction "VDD_3_3") (pintype "power_in"))
      (node (ref "U59") (pin "4") (pinfunction "VDD_4_4") (pintype "power_in"))
    )
    (net (code "49") (name "VDD_3V3_SW") (class "Default")
      (node (ref "C280") (pin "1") (pinfunction "1_1") (pintype "passive"))
      (node (ref "C281") (pin "1") (pinfunction "1_1") (pintype "passive"))
      (node (ref "C282") (pin "1") (pinfunction "1_1") (pintype "passive"))
      (node (ref "C283") (pin "1") (pinfunction "1_1") (pintype "passive"))
      (node (ref "FB16") (pin "2") (pinfunction "2_2") (pintype "passive"))
      (node (ref "R323") (pin "2") (pinfunction "2_2") (pintype "passive"))
      (node (ref "U57") (pin "20") (pinfunction "VDD_20") (pintype "power_in"))
      (node (ref "U57") (pin "5") (pinfunction "VDD_5") (pintype "power_in"))
      (node (ref "U57") (pin "9") (pinfunction "VDD_9") (pintype "power_in"))
    )
    (net (code "50") (name "VDD_5V0_VBUS") (class "Default")
      (node (ref "C275") (pin "1") (pinfunction "1_1") (pintype "passive"))
      (node (ref "C276") (pin "1") (pinfunction "1_1") (pintype "passive"))
      (node (ref "C277") (pin "1") (pinfunction "1_1") (pintype "passive"))
      (node (ref "C278") (pin "1") (pinfunction "1_1") (pintype "passive"))
      (node (ref "C279") (pin "1") (pinfunction "1_1") (pintype "passive"))
      (node (ref "CON12") (pin "A4") (pinfunction "VBUS1_A4") (pintype "passive"))
      (node (ref "CON12") (pin "A9") (pinfunction "VBUS2_A9") (pintype "passive"))
      (node (ref "CON12") (pin "B4") (pinfunction "VBUS3_B4") (pintype "passive"))
      (node (ref "CON12") (pin "B9") (pinfunction "VBUS4_B9") (pintype "passive"))
      (node (ref "R317") (pin "2") (pinfunction "2_2") (pintype "passive"))
      (node (ref "U55") (pin "1") (pinfunction "OUT_1") (pintype "passive"))
      (node (ref "U56") (pin "5") (pinfunction "5_5") (pintype "passive"))
      (node (ref "U59") (pin "2") (pinfunction "VBUS_2") (pintype "passive"))
    )
    (net (code "51") (name "VDD_5V_MAIN") (class "Default")
      (node (ref "C273") (pin "1") (pinfunction "1_1") (pintype "passive"))
      (node (ref "C274") (pin "1") (pinfunction "1_1") (pintype "passive"))
      (node (ref "R316") (pin "1") (pinfunction "1_1") (pintype "passive"))
      (node (ref "U55") (pin "5") (pinfunction "IN_5") (pintype "passive"))
      (node (ref "U59") (pin "12") (pinfunction "VCONN_12_12") (pintype "passive"))
      (node (ref "U59") (pin "13") (pinfunction "VCONN_13_13") (pintype "passive"))
    )
    (net (code "52") (name "XL9555_P14{slash}USB_DRD0_SWITCH{slash}3V3") (class "Default")
      (node (ref "R323") (pin "1") (pinfunction "1_1") (pintype "passive"))
      (node (ref "R485") (pin "1") (pinfunction "1_1") (pintype "passive"))
      (node (ref "U57") (pin "8") (pinfunction "SEL_8") (pintype "passive"))
    )
    (net (code "53") (name "XL9555_P15{slash}USB_DRD0_PWREN{slash}3V3") (class "Default")
      (node (ref "R319") (pin "1") (pinfunction "1_1") (pintype "passive"))
    )
  )
)
